# ESP_PILOT.net
KiCad netlist of a schematic drawn in EAGLE
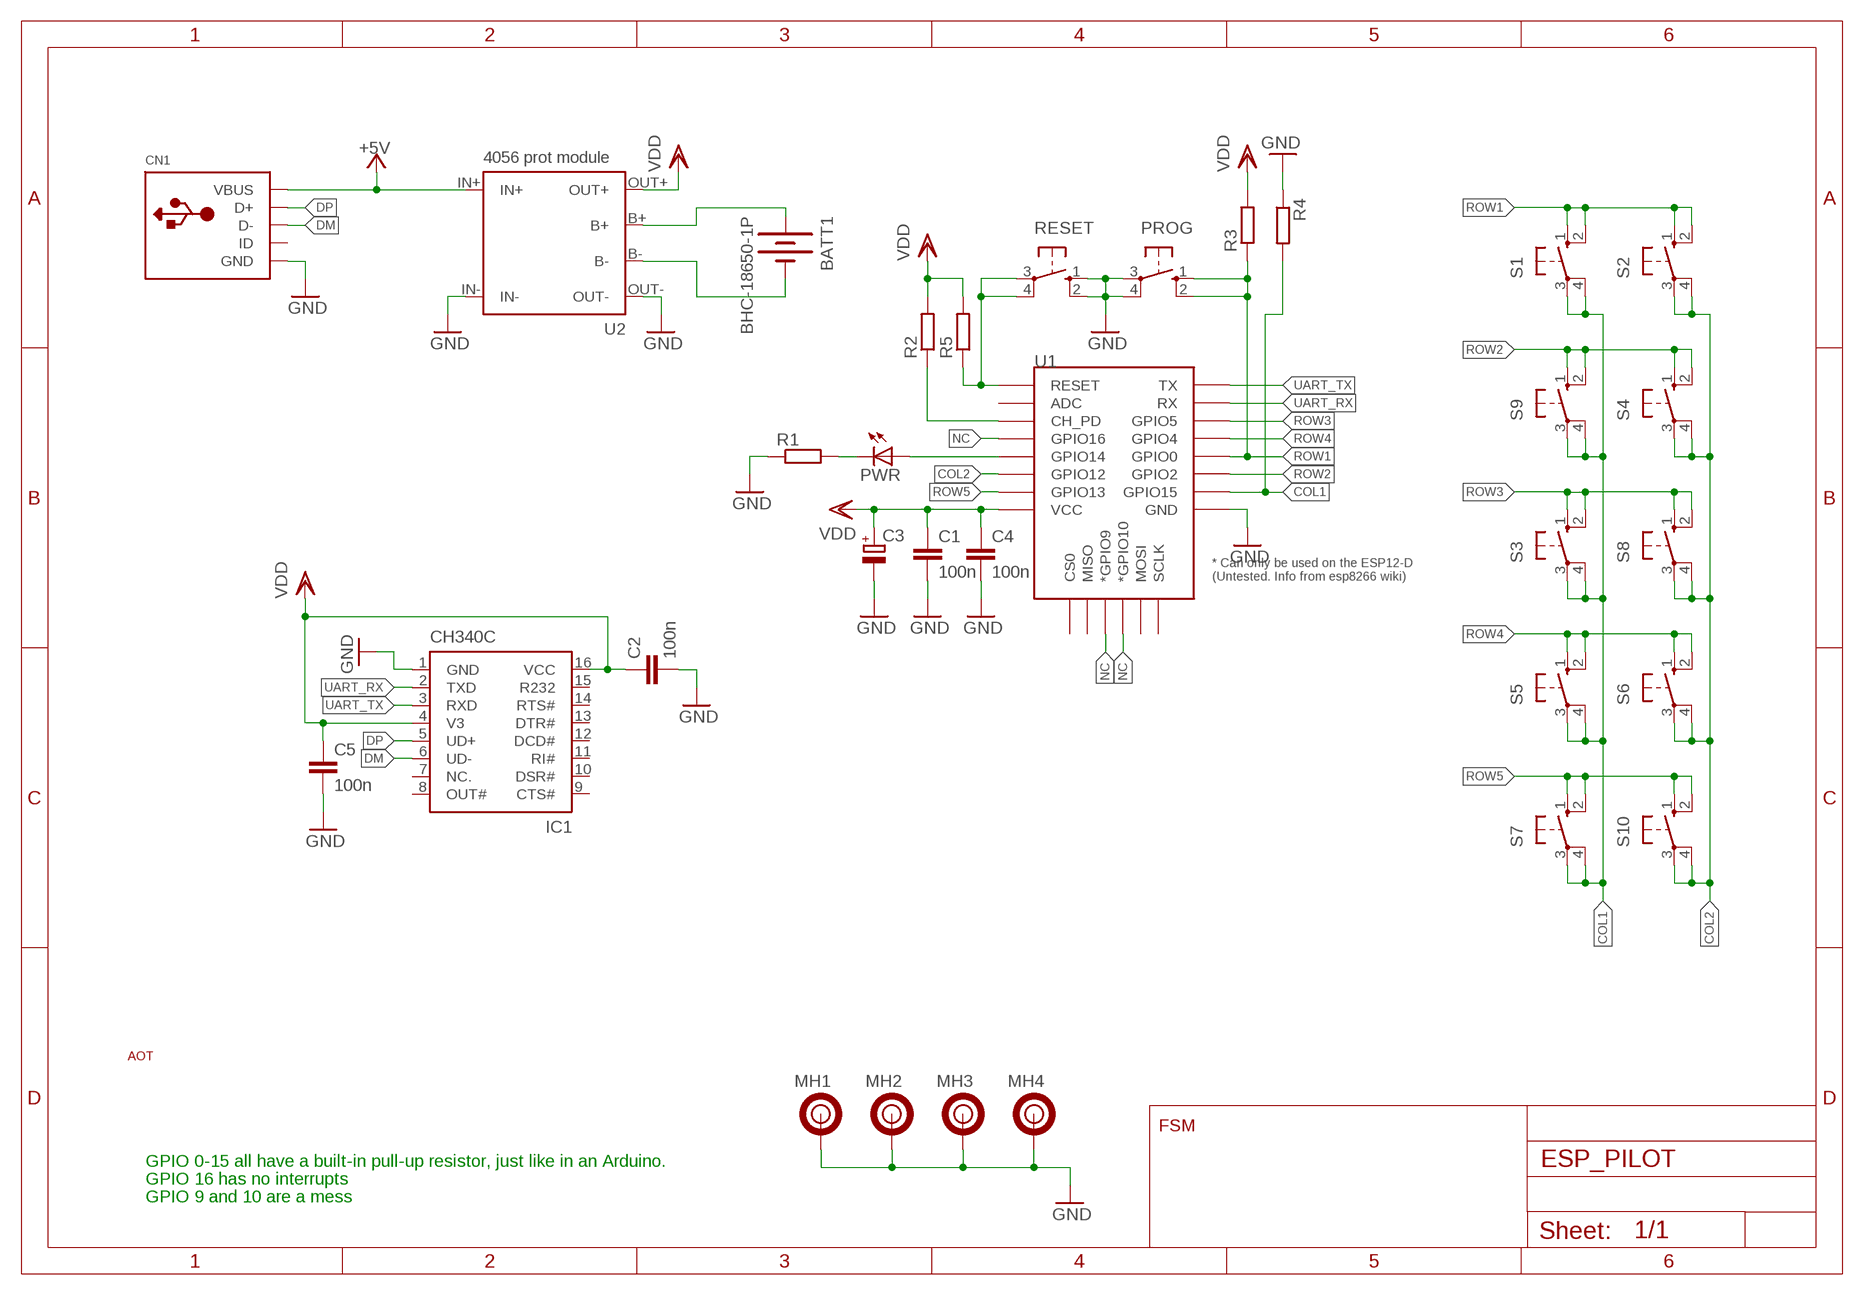
[diagram p0: schematic, sheet 1]

(export (version "E")
  (design (tool "Eeschema 10.0.6"))
  (components
    (comp (ref "BATT1")
      (value "BHC-18650-1P")
      (footprint "eagle-import:BHC-18650-1P")
      (libsource (lib "eagle-import") (part "BHC-18650-1P"))
    )
    (comp (ref "C1")
      (value "100n")
      (footprint "eagle-import:C050-025X075")
      (libsource (lib "eagle-import") (part "C-EU050-025X075"))
    )
    (comp (ref "C2")
      (value "100n")
      (footprint "eagle-import:C050-025X075")
      (libsource (lib "eagle-import") (part "C-EU050-025X075"))
    )
    (comp (ref "C3")
      (value "CPOL-EUE2.5-7")
      (footprint "eagle-import:E2,5-7")
      (libsource (lib "eagle-import") (part "CPOL-EUE2.5-7"))
    )
    (comp (ref "C4")
      (value "100n")
      (footprint "eagle-import:C050-025X075")
      (libsource (lib "eagle-import") (part "C-EU050-025X075"))
    )
    (comp (ref "C5")
      (value "100n")
      (footprint "eagle-import:C050-025X075")
      (libsource (lib "eagle-import") (part "C-EU050-025X075"))
    )
    (comp (ref "CN1")
      (value "USBMINIB")
      (footprint "eagle-import:USB-MINIB")
      (libsource (lib "eagle-import") (part "USBMINIB"))
    )
    (comp (ref "IC1")
      (value "CH340C")
      (footprint "eagle-import:SOIC16N")
      (libsource (lib "eagle-import") (part "CH340C"))
    )
    (comp (ref "MH1")
      (value "MOUNTING_HOLE_3MM")
      (footprint "eagle-import:3MM_CONDUCTING")
      (libsource (lib "eagle-import") (part "MOUNTING_HOLE_3MM"))
    )
    (comp (ref "MH2")
      (value "MOUNTING_HOLE_3MM")
      (footprint "eagle-import:3MM_CONDUCTING")
      (libsource (lib "eagle-import") (part "MOUNTING_HOLE_3MM"))
    )
    (comp (ref "MH3")
      (value "MOUNTING_HOLE_3MM")
      (footprint "eagle-import:3MM_CONDUCTING")
      (libsource (lib "eagle-import") (part "MOUNTING_HOLE_3MM"))
    )
    (comp (ref "MH4")
      (value "MOUNTING_HOLE_3MM")
      (footprint "eagle-import:3MM_CONDUCTING")
      (libsource (lib "eagle-import") (part "MOUNTING_HOLE_3MM"))
    )
    (comp (ref "PROG")
      (value "10-XX")
      (footprint "eagle-import:B3F-10XX")
      (fields (field (name "MPN") "B3F-1000"))
      (libsource (lib "eagle-import") (part "10-XX"))
    )
    (comp (ref "PWR")
      (value "LED5MM")
      (footprint "eagle-import:LED5MM")
      (libsource (lib "eagle-import") (part "LED5MM"))
    )
    (comp (ref "R1")
      (value "R-EU_0207/10")
      (footprint "eagle-import:0207_10")
      (libsource (lib "eagle-import") (part "R-EU_0207/10"))
    )
    (comp (ref "R2")
      (value "R-EU_0207/10")
      (footprint "eagle-import:0207_10")
      (libsource (lib "eagle-import") (part "R-EU_0207/10"))
    )
    (comp (ref "R3")
      (value "R-EU_0207/10")
      (footprint "eagle-import:0207_10")
      (libsource (lib "eagle-import") (part "R-EU_0207/10"))
    )
    (comp (ref "R4")
      (value "R-EU_0207/10")
      (footprint "eagle-import:0207_10")
      (libsource (lib "eagle-import") (part "R-EU_0207/10"))
    )
    (comp (ref "R5")
      (value "R-EU_0207/10")
      (footprint "eagle-import:0207_10")
      (libsource (lib "eagle-import") (part "R-EU_0207/10"))
    )
    (comp (ref "RESET")
      (value "10-XX")
      (footprint "eagle-import:B3F-10XX")
      (fields (field (name "MPN") "B3F-1000"))
      (libsource (lib "eagle-import") (part "10-XX"))
    )
    (comp (ref "S1")
      (value "10-XX")
      (footprint "eagle-import:B3F-10XX")
      (fields (field (name "MPN") "B3F-1000"))
      (libsource (lib "eagle-import") (part "10-XX"))
    )
    (comp (ref "S2")
      (value "10-XX")
      (footprint "eagle-import:B3F-10XX")
      (fields (field (name "MPN") "B3F-1000"))
      (libsource (lib "eagle-import") (part "10-XX"))
    )
    (comp (ref "S3")
      (value "10-XX")
      (footprint "eagle-import:B3F-10XX")
      (fields (field (name "MPN") "B3F-1000"))
      (libsource (lib "eagle-import") (part "10-XX"))
    )
    (comp (ref "S4")
      (value "10-XX")
      (footprint "eagle-import:B3F-10XX")
      (fields (field (name "MPN") "B3F-1000"))
      (libsource (lib "eagle-import") (part "10-XX"))
    )
    (comp (ref "S5")
      (value "10-XX")
      (footprint "eagle-import:B3F-10XX")
      (fields (field (name "MPN") "B3F-1000"))
      (libsource (lib "eagle-import") (part "10-XX"))
    )
    (comp (ref "S6")
      (value "10-XX")
      (footprint "eagle-import:B3F-10XX")
      (fields (field (name "MPN") "B3F-1000"))
      (libsource (lib "eagle-import") (part "10-XX"))
    )
    (comp (ref "S7")
      (value "10-XX")
      (footprint "eagle-import:B3F-10XX")
      (fields (field (name "MPN") "B3F-1000"))
      (libsource (lib "eagle-import") (part "10-XX"))
    )
    (comp (ref "S8")
      (value "10-XX")
      (footprint "eagle-import:B3F-10XX")
      (fields (field (name "MPN") "B3F-1000"))
      (libsource (lib "eagle-import") (part "10-XX"))
    )
    (comp (ref "S9")
      (value "10-XX")
      (footprint "eagle-import:B3F-10XX")
      (fields (field (name "MPN") "B3F-1000"))
      (libsource (lib "eagle-import") (part "10-XX"))
    )
    (comp (ref "S10")
      (value "10-XX")
      (footprint "eagle-import:B3F-10XX")
      (fields (field (name "MPN") "B3F-1000"))
      (libsource (lib "eagle-import") (part "10-XX"))
    )
    (comp (ref "U$1")
      (value "FSM")
      (footprint "eagle-import:FSM")
      (libsource (lib "eagle-import") (part "FSM"))
    )
    (comp (ref "U$2")
      (value "AOT")
      (footprint "eagle-import:AOT")
      (libsource (lib "eagle-import") (part "AOT"))
    )
    (comp (ref "U1")
      (value "ESP12ESMD")
      (footprint "eagle-import:ESP12E-SMD")
      (libsource (lib "eagle-import") (part "ESP12ESMD"))
    )
    (comp (ref "U2")
      (value "4056 prot module")
      (footprint "eagle-import:TP4056_MICRO_MINI_PROT")
      (libsource (lib "eagle-import") (part "TP4056_MICRO/MINI_PROT"))
    )
  )
  (nets
    (net (code "1") (name "+5V") (class "Default")
      (node (ref "CN1") (pin "VBUS") (pinfunction "VBUS_VBUS") (pintype "power_in"))
      (node (ref "U2") (pin "IN+") (pinfunction "IN+_IN+") (pintype "bidirectional"))
    )
    (net (code "2") (name "COL1") (class "Default")
      (node (ref "R4") (pin "2") (pinfunction "2_2") (pintype "passive"))
      (node (ref "S1") (pin "3") (pinfunction "P_3") (pintype "passive"))
      (node (ref "S1") (pin "4") (pinfunction "P1_4") (pintype "passive"))
      (node (ref "S3") (pin "3") (pinfunction "P_3") (pintype "passive"))
      (node (ref "S3") (pin "4") (pinfunction "P1_4") (pintype "passive"))
      (node (ref "S5") (pin "3") (pinfunction "P_3") (pintype "passive"))
      (node (ref "S5") (pin "4") (pinfunction "P1_4") (pintype "passive"))
      (node (ref "S7") (pin "3") (pinfunction "P_3") (pintype "passive"))
      (node (ref "S7") (pin "4") (pinfunction "P1_4") (pintype "passive"))
      (node (ref "S9") (pin "3") (pinfunction "P_3") (pintype "passive"))
      (node (ref "S9") (pin "4") (pinfunction "P1_4") (pintype "passive"))
      (node (ref "U1") (pin "GPIO15") (pinfunction "GPIO15_GPIO15") (pintype "bidirectional"))
    )
    (net (code "3") (name "COL2") (class "Default")
      (node (ref "S10") (pin "3") (pinfunction "P_3") (pintype "passive"))
      (node (ref "S10") (pin "4") (pinfunction "P1_4") (pintype "passive"))
      (node (ref "S2") (pin "3") (pinfunction "P_3") (pintype "passive"))
      (node (ref "S2") (pin "4") (pinfunction "P1_4") (pintype "passive"))
      (node (ref "S4") (pin "3") (pinfunction "P_3") (pintype "passive"))
      (node (ref "S4") (pin "4") (pinfunction "P1_4") (pintype "passive"))
      (node (ref "S6") (pin "3") (pinfunction "P_3") (pintype "passive"))
      (node (ref "S6") (pin "4") (pinfunction "P1_4") (pintype "passive"))
      (node (ref "S8") (pin "3") (pinfunction "P_3") (pintype "passive"))
      (node (ref "S8") (pin "4") (pinfunction "P1_4") (pintype "passive"))
      (node (ref "U1") (pin "GPIO12") (pinfunction "GPIO12_GPIO12") (pintype "bidirectional"))
    )
    (net (code "4") (name "DM") (class "Default")
      (node (ref "CN1") (pin "D-") (pinfunction "D-_D-") (pintype "bidirectional"))
      (node (ref "IC1") (pin "6") (pinfunction "UD-_6") (pintype "bidirectional"))
    )
    (net (code "5") (name "DP") (class "Default")
      (node (ref "CN1") (pin "D+") (pinfunction "D+_D+") (pintype "bidirectional"))
      (node (ref "IC1") (pin "5") (pinfunction "UD+_5") (pintype "bidirectional"))
    )
    (net (code "6") (name "GND") (class "Default")
      (node (ref "C1") (pin "2") (pinfunction "2_2") (pintype "passive"))
      (node (ref "C2") (pin "2") (pinfunction "2_2") (pintype "passive"))
      (node (ref "C3") (pin "-") (pinfunction "-_-") (pintype "passive"))
      (node (ref "C4") (pin "2") (pinfunction "2_2") (pintype "passive"))
      (node (ref "C5") (pin "2") (pinfunction "2_2") (pintype "passive"))
      (node (ref "CN1") (pin "GND") (pinfunction "GND_GND") (pintype "power_in"))
      (node (ref "IC1") (pin "1") (pinfunction "GND_1") (pintype "bidirectional"))
      (node (ref "MH1") (pin "1") (pinfunction "P$1_1") (pintype "bidirectional"))
      (node (ref "MH1") (pin "2") (pinfunction "P$1_2") (pintype "bidirectional"))
      (node (ref "MH1") (pin "3") (pinfunction "P$1_3") (pintype "bidirectional"))
      (node (ref "MH1") (pin "4") (pinfunction "P$1_4") (pintype "bidirectional"))
      (node (ref "MH1") (pin "5") (pinfunction "P$1_5") (pintype "bidirectional"))
      (node (ref "MH1") (pin "6") (pinfunction "P$1_6") (pintype "bidirectional"))
      (node (ref "MH1") (pin "7") (pinfunction "P$1_7") (pintype "bidirectional"))
      (node (ref "MH1") (pin "8") (pinfunction "P$1_8") (pintype "bidirectional"))
      (node (ref "MH1") (pin "O") (pinfunction "P$1_O") (pintype "bidirectional"))
      (node (ref "MH2") (pin "1") (pinfunction "P$1_1") (pintype "bidirectional"))
      (node (ref "MH2") (pin "2") (pinfunction "P$1_2") (pintype "bidirectional"))
      (node (ref "MH2") (pin "3") (pinfunction "P$1_3") (pintype "bidirectional"))
      (node (ref "MH2") (pin "4") (pinfunction "P$1_4") (pintype "bidirectional"))
      (node (ref "MH2") (pin "5") (pinfunction "P$1_5") (pintype "bidirectional"))
      (node (ref "MH2") (pin "6") (pinfunction "P$1_6") (pintype "bidirectional"))
      (node (ref "MH2") (pin "7") (pinfunction "P$1_7") (pintype "bidirectional"))
      (node (ref "MH2") (pin "8") (pinfunction "P$1_8") (pintype "bidirectional"))
      (node (ref "MH2") (pin "O") (pinfunction "P$1_O") (pintype "bidirectional"))
      (node (ref "MH3") (pin "1") (pinfunction "P$1_1") (pintype "bidirectional"))
      (node (ref "MH3") (pin "2") (pinfunction "P$1_2") (pintype "bidirectional"))
      (node (ref "MH3") (pin "3") (pinfunction "P$1_3") (pintype "bidirectional"))
      (node (ref "MH3") (pin "4") (pinfunction "P$1_4") (pintype "bidirectional"))
      (node (ref "MH3") (pin "5") (pinfunction "P$1_5") (pintype "bidirectional"))
      (node (ref "MH3") (pin "6") (pinfunction "P$1_6") (pintype "bidirectional"))
      (node (ref "MH3") (pin "7") (pinfunction "P$1_7") (pintype "bidirectional"))
      (node (ref "MH3") (pin "8") (pinfunction "P$1_8") (pintype "bidirectional"))
      (node (ref "MH3") (pin "O") (pinfunction "P$1_O") (pintype "bidirectional"))
      (node (ref "MH4") (pin "1") (pinfunction "P$1_1") (pintype "bidirectional"))
      (node (ref "MH4") (pin "2") (pinfunction "P$1_2") (pintype "bidirectional"))
      (node (ref "MH4") (pin "3") (pinfunction "P$1_3") (pintype "bidirectional"))
      (node (ref "MH4") (pin "4") (pinfunction "P$1_4") (pintype "bidirectional"))
      (node (ref "MH4") (pin "5") (pinfunction "P$1_5") (pintype "bidirectional"))
      (node (ref "MH4") (pin "6") (pinfunction "P$1_6") (pintype "bidirectional"))
      (node (ref "MH4") (pin "7") (pinfunction "P$1_7") (pintype "bidirectional"))
      (node (ref "MH4") (pin "8") (pinfunction "P$1_8") (pintype "bidirectional"))
      (node (ref "MH4") (pin "O") (pinfunction "P$1_O") (pintype "bidirectional"))
      (node (ref "PROG") (pin "3") (pinfunction "P_3") (pintype "passive"))
      (node (ref "PROG") (pin "4") (pinfunction "P1_4") (pintype "passive"))
      (node (ref "R1") (pin "1") (pinfunction "1_1") (pintype "passive"))
      (node (ref "R4") (pin "1") (pinfunction "1_1") (pintype "passive"))
      (node (ref "RESET") (pin "1") (pinfunction "S_1") (pintype "passive"))
      (node (ref "RESET") (pin "2") (pinfunction "S1_2") (pintype "passive"))
      (node (ref "U1") (pin "GND") (pinfunction "GND_GND") (pintype "bidirectional"))
      (node (ref "U2") (pin "IN-") (pinfunction "IN-_IN-") (pintype "bidirectional"))
      (node (ref "U2") (pin "OUT-") (pinfunction "OUT-_OUT-") (pintype "bidirectional"))
    )
    (net (code "7") (name "NC") (class "Default")
      (node (ref "U1") (pin "GPIO10") (pinfunction "*GPIO10_GPIO10") (pintype "bidirectional"))
      (node (ref "U1") (pin "GPIO16") (pinfunction "GPIO16_GPIO16") (pintype "bidirectional"))
      (node (ref "U1") (pin "GPIO9") (pinfunction "*GPIO9_GPIO9") (pintype "bidirectional"))
    )
    (net (code "8") (name "Net-(BATT1-+)") (class "Default")
      (node (ref "BATT1") (pin "-") (pinfunction "+_-") (pintype "power_in"))
      (node (ref "U2") (pin "B+") (pinfunction "B+_B+") (pintype "bidirectional"))
    )
    (net (code "9") (name "Net-(BATT1--)") (class "Default")
      (node (ref "BATT1") (pin "+") (pinfunction "-_+") (pintype "power_in"))
      (node (ref "U2") (pin "B-") (pinfunction "B-_B-") (pintype "bidirectional"))
    )
    (net (code "10") (name "Net-(PWR-C)") (class "Default")
      (node (ref "PWR") (pin "K") (pinfunction "C_K") (pintype "passive"))
      (node (ref "R1") (pin "2") (pinfunction "2_2") (pintype "passive"))
    )
    (net (code "11") (name "Net-(PWR-PadA)") (class "Default")
      (node (ref "PWR") (pin "A") (pinfunction "A_A") (pintype "passive"))
      (node (ref "U1") (pin "GPIO14") (pinfunction "GPIO14_GPIO14") (pintype "bidirectional"))
    )
    (net (code "12") (name "Net-(R2-Pad1)") (class "Default")
      (node (ref "R2") (pin "1") (pinfunction "1_1") (pintype "passive"))
      (node (ref "U1") (pin "CH_PD") (pinfunction "CH_PD_CH_PD") (pintype "bidirectional"))
    )
    (net (code "13") (name "Net-(RESET-P)") (class "Default")
      (node (ref "R5") (pin "1") (pinfunction "1_1") (pintype "passive"))
      (node (ref "RESET") (pin "3") (pinfunction "P_3") (pintype "passive"))
      (node (ref "RESET") (pin "4") (pinfunction "P1_4") (pintype "passive"))
      (node (ref "U1") (pin "RESET") (pinfunction "RESET_RESET") (pintype "bidirectional"))
    )
    (net (code "14") (name "ROW1") (class "Default")
      (node (ref "PROG") (pin "1") (pinfunction "S_1") (pintype "passive"))
      (node (ref "PROG") (pin "2") (pinfunction "S1_2") (pintype "passive"))
      (node (ref "R3") (pin "1") (pinfunction "1_1") (pintype "passive"))
      (node (ref "S1") (pin "1") (pinfunction "S_1") (pintype "passive"))
      (node (ref "S1") (pin "2") (pinfunction "S1_2") (pintype "passive"))
      (node (ref "S2") (pin "1") (pinfunction "S_1") (pintype "passive"))
      (node (ref "S2") (pin "2") (pinfunction "S1_2") (pintype "passive"))
      (node (ref "U1") (pin "GPIO0") (pinfunction "GPIO0_GPIO0") (pintype "bidirectional"))
    )
    (net (code "15") (name "ROW2") (class "Default")
      (node (ref "S4") (pin "1") (pinfunction "S_1") (pintype "passive"))
      (node (ref "S4") (pin "2") (pinfunction "S1_2") (pintype "passive"))
      (node (ref "S9") (pin "1") (pinfunction "S_1") (pintype "passive"))
      (node (ref "S9") (pin "2") (pinfunction "S1_2") (pintype "passive"))
      (node (ref "U1") (pin "GPIO2") (pinfunction "GPIO2_GPIO2") (pintype "bidirectional"))
    )
    (net (code "16") (name "ROW3") (class "Default")
      (node (ref "S3") (pin "1") (pinfunction "S_1") (pintype "passive"))
      (node (ref "S3") (pin "2") (pinfunction "S1_2") (pintype "passive"))
      (node (ref "S8") (pin "1") (pinfunction "S_1") (pintype "passive"))
      (node (ref "S8") (pin "2") (pinfunction "S1_2") (pintype "passive"))
      (node (ref "U1") (pin "GPIO5") (pinfunction "GPIO5_GPIO5") (pintype "bidirectional"))
    )
    (net (code "17") (name "ROW4") (class "Default")
      (node (ref "S5") (pin "1") (pinfunction "S_1") (pintype "passive"))
      (node (ref "S5") (pin "2") (pinfunction "S1_2") (pintype "passive"))
      (node (ref "S6") (pin "1") (pinfunction "S_1") (pintype "passive"))
      (node (ref "S6") (pin "2") (pinfunction "S1_2") (pintype "passive"))
      (node (ref "U1") (pin "GPIO4") (pinfunction "GPIO4_GPIO4") (pintype "bidirectional"))
    )
    (net (code "18") (name "ROW5") (class "Default")
      (node (ref "S10") (pin "1") (pinfunction "S_1") (pintype "passive"))
      (node (ref "S10") (pin "2") (pinfunction "S1_2") (pintype "passive"))
      (node (ref "S7") (pin "1") (pinfunction "S_1") (pintype "passive"))
      (node (ref "S7") (pin "2") (pinfunction "S1_2") (pintype "passive"))
      (node (ref "U1") (pin "GPIO13") (pinfunction "GPIO13_GPIO13") (pintype "bidirectional"))
    )
    (net (code "19") (name "UART_RX") (class "Default")
      (node (ref "IC1") (pin "2") (pinfunction "TXD_2") (pintype "bidirectional"))
      (node (ref "U1") (pin "RXD0") (pinfunction "RX_RXD0") (pintype "bidirectional"))
    )
    (net (code "20") (name "UART_TX") (class "Default")
      (node (ref "IC1") (pin "3") (pinfunction "RXD_3") (pintype "bidirectional"))
      (node (ref "U1") (pin "TXD0") (pinfunction "TX_TXD0") (pintype "bidirectional"))
    )
    (net (code "21") (name "VDD") (class "Default")
      (node (ref "C1") (pin "1") (pinfunction "1_1") (pintype "passive"))
      (node (ref "C2") (pin "1") (pinfunction "1_1") (pintype "passive"))
      (node (ref "C3") (pin "+") (pinfunction "+_+") (pintype "passive"))
      (node (ref "C4") (pin "1") (pinfunction "1_1") (pintype "passive"))
      (node (ref "C5") (pin "1") (pinfunction "1_1") (pintype "passive"))
      (node (ref "IC1") (pin "16") (pinfunction "VCC_16") (pintype "bidirectional"))
      (node (ref "IC1") (pin "4") (pinfunction "V3_4") (pintype "bidirectional"))
      (node (ref "R2") (pin "2") (pinfunction "2_2") (pintype "passive"))
      (node (ref "R3") (pin "2") (pinfunction "2_2") (pintype "passive"))
      (node (ref "R5") (pin "2") (pinfunction "2_2") (pintype "passive"))
      (node (ref "U1") (pin "VCC") (pinfunction "VCC_VCC") (pintype "bidirectional"))
      (node (ref "U2") (pin "OUT+") (pinfunction "OUT+_OUT+") (pintype "bidirectional"))
    )
    (net (code "22") (name "unconnected-(CN1-PadID)") (class "Default")
      (node (ref "CN1") (pin "ID") (pinfunction "ID_ID") (pintype "bidirectional"))
    )
    (net (code "23") (name "unconnected-(IC1-CTS#-Pad9)") (class "Default")
      (node (ref "IC1") (pin "9") (pinfunction "CTS#_9") (pintype "bidirectional"))
    )
    (net (code "24") (name "unconnected-(IC1-DCD#-Pad12)") (class "Default")
      (node (ref "IC1") (pin "12") (pinfunction "DCD#_12") (pintype "bidirectional"))
    )
    (net (code "25") (name "unconnected-(IC1-DSR#-Pad10)") (class "Default")
      (node (ref "IC1") (pin "10") (pinfunction "DSR#_10") (pintype "bidirectional"))
    )
    (net (code "26") (name "unconnected-(IC1-DTR#-Pad13)") (class "Default")
      (node (ref "IC1") (pin "13") (pinfunction "DTR#_13") (pintype "bidirectional"))
    )
    (net (code "27") (name "unconnected-(IC1-NC.-Pad7)") (class "Default")
      (node (ref "IC1") (pin "7") (pinfunction "NC._7") (pintype "bidirectional"))
    )
    (net (code "28") (name "unconnected-(IC1-OUT#-Pad8)") (class "Default")
      (node (ref "IC1") (pin "8") (pinfunction "OUT#_8") (pintype "bidirectional"))
    )
    (net (code "29") (name "unconnected-(IC1-R232-Pad15)") (class "Default")
      (node (ref "IC1") (pin "15") (pinfunction "R232_15") (pintype "bidirectional"))
    )
    (net (code "30") (name "unconnected-(IC1-RI#-Pad11)") (class "Default")
      (node (ref "IC1") (pin "11") (pinfunction "RI#_11") (pintype "bidirectional"))
    )
    (net (code "31") (name "unconnected-(IC1-RTS#-Pad14)") (class "Default")
      (node (ref "IC1") (pin "14") (pinfunction "RTS#_14") (pintype "bidirectional"))
    )
    (net (code "32") (name "unconnected-(U1-PadADC)") (class "Default")
      (node (ref "U1") (pin "ADC") (pinfunction "ADC_ADC") (pintype "bidirectional"))
    )
    (net (code "33") (name "unconnected-(U1-PadCS0)") (class "Default")
      (node (ref "U1") (pin "CS0") (pinfunction "CS0_CS0") (pintype "bidirectional"))
    )
    (net (code "34") (name "unconnected-(U1-PadMISO)") (class "Default")
      (node (ref "U1") (pin "MISO") (pinfunction "MISO_MISO") (pintype "bidirectional"))
    )
    (net (code "35") (name "unconnected-(U1-PadMOSI)") (class "Default")
      (node (ref "U1") (pin "MOSI") (pinfunction "MOSI_MOSI") (pintype "bidirectional"))
    )
    (net (code "36") (name "unconnected-(U1-PadSCLK)") (class "Default")
      (node (ref "U1") (pin "SCLK") (pinfunction "SCLK_SCLK") (pintype "bidirectional"))
    )
  )
)
